# LCLFilter_Updated.net
KiCad netlist of a schematic drawn in Altium Designer
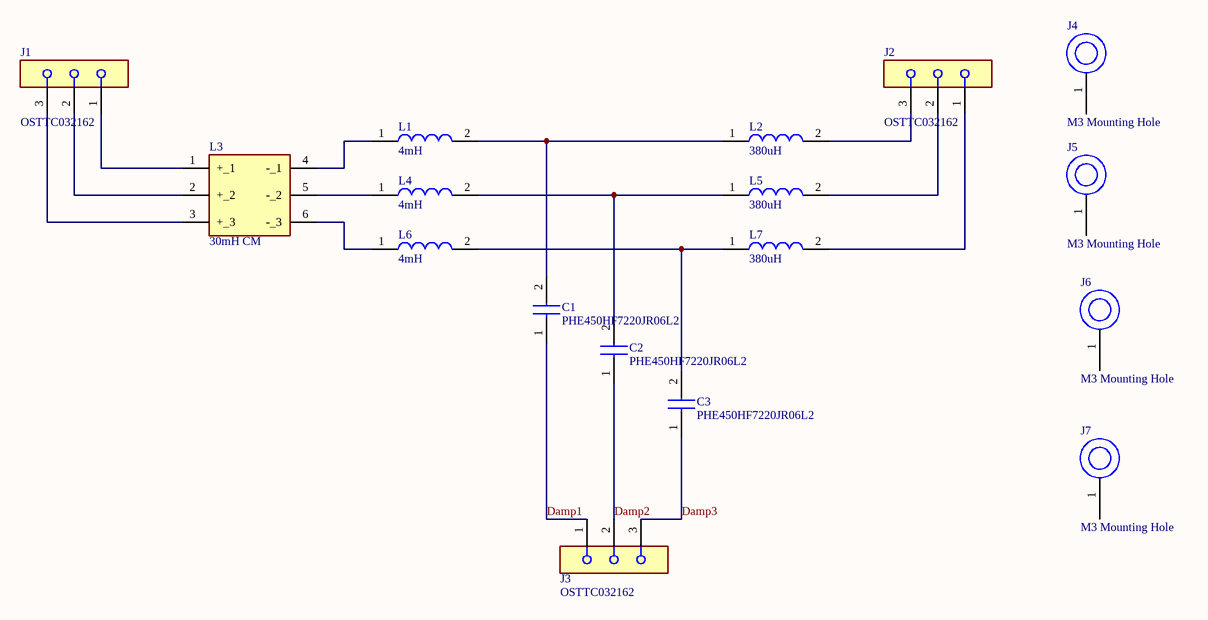
[diagram p0: LCLFilter_Updated.SchDoc]

(export (version "E")
  (design (tool "Eeschema 10.0.6"))
  (components
    (comp (ref "C1")
      (value "PHE450HF7220JR06L2")
      (footprint "Film Capacitor PHE450HF7220JR06L2")
      (description "Capacitor")
      (libsource (lib "FYP_Components") (part "PHE450HF7220JR06L2"))
    )
    (comp (ref "C2")
      (value "PHE450HF7220JR06L2")
      (footprint "Film Capacitor PHE450HF7220JR06L2")
      (description "Capacitor")
      (libsource (lib "FYP_Components") (part "PHE450HF7220JR06L2"))
    )
    (comp (ref "C3")
      (value "PHE450HF7220JR06L2")
      (footprint "Film Capacitor PHE450HF7220JR06L2")
      (description "Capacitor")
      (libsource (lib "FYP_Components") (part "PHE450HF7220JR06L2"))
    )
    (comp (ref "J1")
      (value "3PinTerminal")
      (footprint "3 Pin Terminal")
      (description "3 Position Terminal Block 5.08mm")
      (fields
        (field (name "VOLTAGE") "300V")
        (field (name "MANUFACTURER") "On Shore Technology")
        (field (name "PART NUMBER") "OSTTC032162")
      )
      (libsource (lib "FYP_Components") (part "3PinTerminal"))
    )
    (comp (ref "J2")
      (value "3PinTerminal")
      (footprint "3 Pin Terminal")
      (description "3 Position Terminal Block 5.08mm")
      (fields
        (field (name "VOLTAGE") "300V")
        (field (name "MANUFACTURER") "On Shore Technology")
        (field (name "PART NUMBER") "OSTTC032162")
      )
      (libsource (lib "FYP_Components") (part "3PinTerminal"))
    )
    (comp (ref "J3")
      (value "3PinTerminal")
      (footprint "3 Pin Terminal")
      (description "3 Position Terminal Block 5.08mm")
      (fields
        (field (name "VOLTAGE") "300V")
        (field (name "MANUFACTURER") "On Shore Technology")
        (field (name "PART NUMBER") "OSTTC032162")
      )
      (libsource (lib "") (part "3PinTerminal_1"))
    )
    (comp (ref "J4")
      (value "M3 Mounting Hole")
      (footprint "M3 Mounting Hole")
      (libsource (lib "FYP_Components") (part "M3 Mounting Hole"))
    )
    (comp (ref "J5")
      (value "M3 Mounting Hole")
      (footprint "M3 Mounting Hole")
      (libsource (lib "FYP_Components") (part "M3 Mounting Hole"))
    )
    (comp (ref "J6")
      (value "M3 Mounting Hole")
      (footprint "M3 Mounting Hole")
      (libsource (lib "FYP_Components") (part "M3 Mounting Hole"))
    )
    (comp (ref "J7")
      (value "M3 Mounting Hole")
      (footprint "M3 Mounting Hole")
      (libsource (lib "FYP_Components") (part "M3 Mounting Hole"))
    )
    (comp (ref "L1")
      (value "4mH")
      (footprint "4mH Custom")
      (libsource (lib "FYP_Components") (part "4mH Custom Inductor"))
    )
    (comp (ref "L2")
      (value "380uH")
      (footprint "380uH Custom")
      (libsource (lib "FYP_Components") (part "380uH Custom Inductor"))
    )
    (comp (ref "L3")
      (value "30mH CM")
      (footprint "FYP_Components:CM Choke Custom")
      (description "30mH Custom CM Choke")
      (fields
        (field (name "MANUFACTURER_PART_NUMBER") "744839029220")
        (field (name "MOUSER PART NUMBER") "710-744839029220")
      )
      (libsource (lib "FYP_Components") (part "30mH Custom CM Choke"))
    )
    (comp (ref "L4")
      (value "4mH")
      (footprint "4mH Custom")
      (libsource (lib "FYP_Components") (part "4mH Custom Inductor"))
    )
    (comp (ref "L5")
      (value "380uH")
      (footprint "380uH Custom")
      (libsource (lib "FYP_Components") (part "380uH Custom Inductor"))
    )
    (comp (ref "L6")
      (value "4mH")
      (footprint "4mH Custom")
      (libsource (lib "FYP_Components") (part "4mH Custom Inductor"))
    )
    (comp (ref "L7")
      (value "380uH")
      (footprint "380uH Custom")
      (libsource (lib "FYP_Components") (part "380uH Custom Inductor"))
    )
  )
  (nets
    (net (code "1") (name "/Damp1") (class "Default")
      (node (ref "C1") (pin "1") (pinfunction "1_1") (pintype "passive"))
      (node (ref "J3") (pin "1") (pinfunction "1_1") (pintype "passive"))
    )
    (net (code "2") (name "/Damp2") (class "Default")
      (node (ref "C2") (pin "1") (pinfunction "1_1") (pintype "passive"))
      (node (ref "J3") (pin "2") (pinfunction "2_2") (pintype "passive"))
    )
    (net (code "3") (name "/Damp3") (class "Default")
      (node (ref "C3") (pin "1") (pinfunction "1_1") (pintype "passive"))
      (node (ref "J3") (pin "3") (pinfunction "3_3") (pintype "passive"))
    )
    (net (code "4") (name "Net-(C1-Pad2)") (class "Default")
      (node (ref "C1") (pin "2") (pinfunction "2_2") (pintype "passive"))
      (node (ref "L1") (pin "2") (pinfunction "2_2") (pintype "passive"))
      (node (ref "L2") (pin "1") (pinfunction "1_1") (pintype "passive"))
    )
    (net (code "5") (name "Net-(C2-Pad2)") (class "Default")
      (node (ref "C2") (pin "2") (pinfunction "2_2") (pintype "passive"))
      (node (ref "L4") (pin "2") (pinfunction "2_2") (pintype "passive"))
      (node (ref "L5") (pin "1") (pinfunction "1_1") (pintype "passive"))
    )
    (net (code "6") (name "Net-(C3-Pad2)") (class "Default")
      (node (ref "C3") (pin "2") (pinfunction "2_2") (pintype "passive"))
      (node (ref "L6") (pin "2") (pinfunction "2_2") (pintype "passive"))
      (node (ref "L7") (pin "1") (pinfunction "1_1") (pintype "passive"))
    )
    (net (code "7") (name "Net-(J2-Pad1)") (class "Default")
      (node (ref "J2") (pin "1") (pinfunction "1_1") (pintype "passive"))
      (node (ref "L7") (pin "2") (pinfunction "2_2") (pintype "passive"))
    )
    (net (code "8") (name "Net-(J2-Pad2)") (class "Default")
      (node (ref "J2") (pin "2") (pinfunction "2_2") (pintype "passive"))
      (node (ref "L5") (pin "2") (pinfunction "2_2") (pintype "passive"))
    )
    (net (code "9") (name "Net-(J2-Pad3)") (class "Default")
      (node (ref "J2") (pin "3") (pinfunction "3_3") (pintype "passive"))
      (node (ref "L2") (pin "2") (pinfunction "2_2") (pintype "passive"))
    )
    (net (code "10") (name "Net-(L3-+_1)") (class "Default")
      (node (ref "J1") (pin "1") (pinfunction "1_1") (pintype "passive"))
      (node (ref "L3") (pin "1") (pinfunction "+_1_1") (pintype "passive"))
    )
    (net (code "11") (name "Net-(L3-+_2)") (class "Default")
      (node (ref "J1") (pin "2") (pinfunction "2_2") (pintype "passive"))
      (node (ref "L3") (pin "2") (pinfunction "+_2_2") (pintype "passive"))
    )
    (net (code "12") (name "Net-(L3-+_3)") (class "Default")
      (node (ref "J1") (pin "3") (pinfunction "3_3") (pintype "passive"))
      (node (ref "L3") (pin "3") (pinfunction "+_3_3") (pintype "passive"))
    )
    (net (code "13") (name "Net-(L3--_1)") (class "Default")
      (node (ref "L1") (pin "1") (pinfunction "1_1") (pintype "passive"))
      (node (ref "L3") (pin "4") (pinfunction "-_1_4") (pintype "passive"))
    )
    (net (code "14") (name "Net-(L3--_2)") (class "Default")
      (node (ref "L3") (pin "5") (pinfunction "-_2_5") (pintype "passive"))
      (node (ref "L4") (pin "1") (pinfunction "1_1") (pintype "passive"))
    )
    (net (code "15") (name "Net-(L3--_3)") (class "Default")
      (node (ref "L3") (pin "6") (pinfunction "-_3_6") (pintype "passive"))
      (node (ref "L6") (pin "1") (pinfunction "1_1") (pintype "passive"))
    )
    (net (code "16") (name "unconnected-(J4-Pad1)") (class "Default")
      (node (ref "J4") (pin "1") (pinfunction "1_1") (pintype "passive"))
    )
    (net (code "17") (name "unconnected-(J5-Pad1)") (class "Default")
      (node (ref "J5") (pin "1") (pinfunction "1_1") (pintype "passive"))
    )
    (net (code "18") (name "unconnected-(J6-Pad1)") (class "Default")
      (node (ref "J6") (pin "1") (pinfunction "1_1") (pintype "passive"))
    )
    (net (code "19") (name "unconnected-(J7-Pad1)") (class "Default")
      (node (ref "J7") (pin "1") (pinfunction "1_1") (pintype "passive"))
    )
  )
)
